# Caurin_CDH_v_1_0.net
KiCad netlist of a schematic drawn in EAGLE
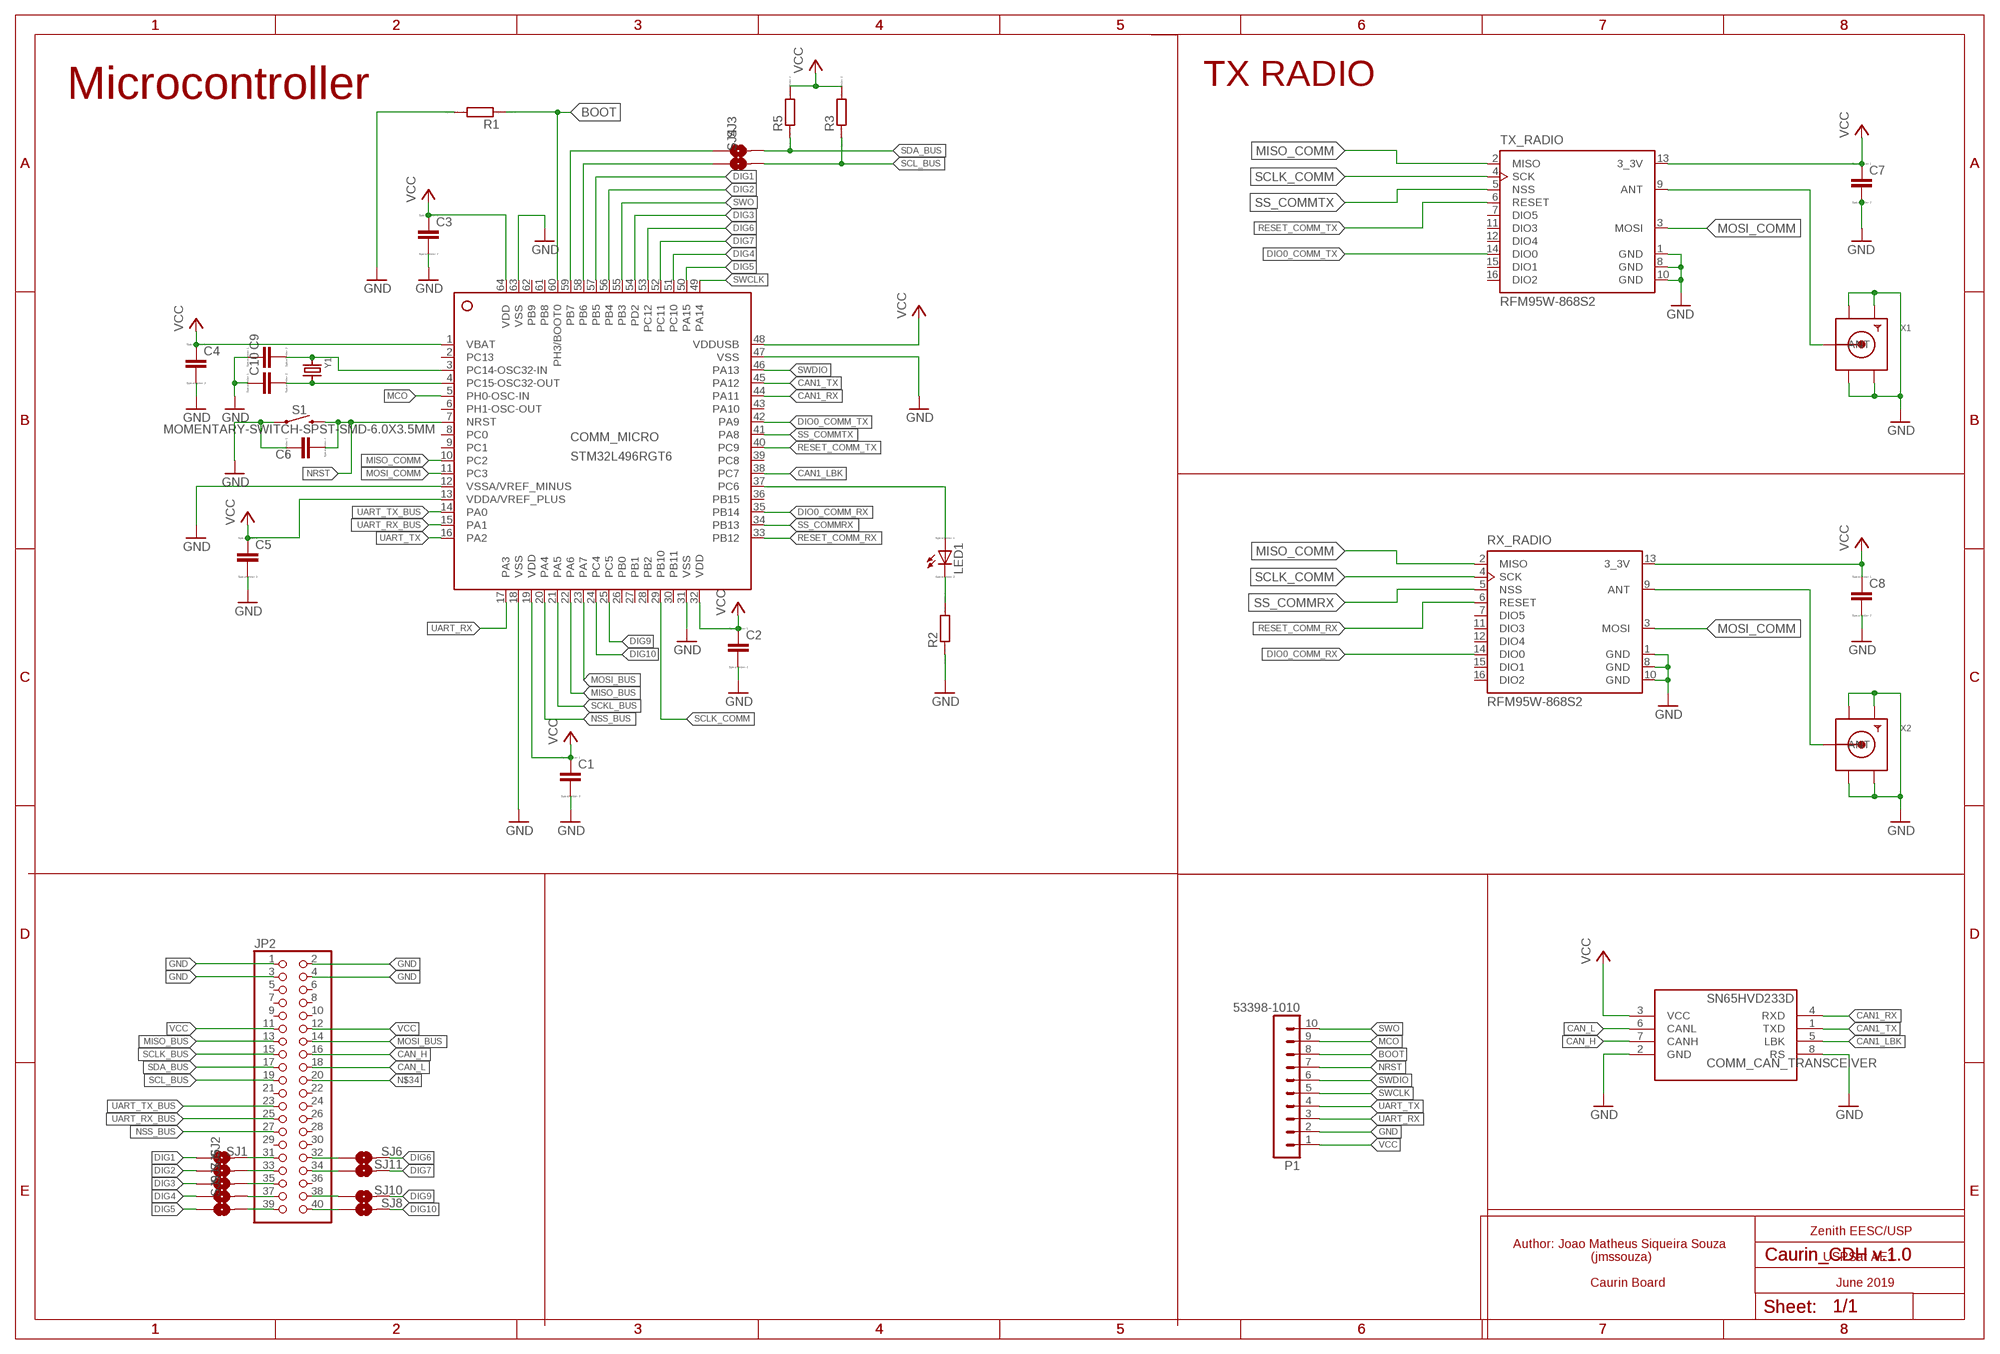
[diagram p0: schematic, sheet 1]

(export (version "E")
  (design (tool "Eeschema 10.0.6"))
  (components
    (comp (ref "C1")
      (value "CC1206")
      (footprint "eagle-import:C1206")
      (libsource (lib "eagle-import") (part "eagle-ltspice_217_CC1206"))
    )
    (comp (ref "C2")
      (value "CC1206")
      (footprint "eagle-import:C1206")
      (libsource (lib "eagle-import") (part "eagle-ltspice_217_CC1206"))
    )
    (comp (ref "C3")
      (value "CC1206")
      (footprint "eagle-import:C1206")
      (libsource (lib "eagle-import") (part "eagle-ltspice_217_CC1206"))
    )
    (comp (ref "C4")
      (value "CC1206")
      (footprint "eagle-import:C1206")
      (libsource (lib "eagle-import") (part "eagle-ltspice_217_CC1206"))
    )
    (comp (ref "C5")
      (value "CC1206")
      (footprint "eagle-import:C1206")
      (libsource (lib "eagle-import") (part "eagle-ltspice_217_CC1206"))
    )
    (comp (ref "C6")
      (value "CC1206")
      (footprint "eagle-import:C1206")
      (libsource (lib "eagle-import") (part "eagle-ltspice_217_CC1206"))
    )
    (comp (ref "C7")
      (value "CC1206")
      (footprint "eagle-import:C1206")
      (libsource (lib "eagle-import") (part "eagle-ltspice_217_CC1206"))
    )
    (comp (ref "C8")
      (value "CC1206")
      (footprint "eagle-import:C1206")
      (libsource (lib "eagle-import") (part "CC1206"))
    )
    (comp (ref "C9")
      (value "CC1206")
      (footprint "eagle-import:C1206")
      (libsource (lib "eagle-import") (part "eagle-ltspice_217_CC1206"))
    )
    (comp (ref "C10")
      (value "CC1206")
      (footprint "eagle-import:C1206")
      (libsource (lib "eagle-import") (part "eagle-ltspice_217_CC1206"))
    )
    (comp (ref "COMM_CAN_TRANSCEIVER")
      (value "SN65HVD233D")
      (footprint "eagle-import:SOIC8")
      (fields (field (name "MF") "Texas Instruments"))
      (libsource (lib "eagle-import") (part "SN65HVD233D"))
    )
    (comp (ref "COMM_MICRO")
      (value "STM32L496RGT6")
      (footprint "eagle-import:LQFP64_10X10")
      (libsource (lib "eagle-import") (part "STM32L496RGT6"))
    )
    (comp (ref "JP2")
      (value "PINHD-2X20")
      (footprint "eagle-import:2X20")
      (libsource (lib "eagle-import") (part "PINHD-2X20"))
    )
    (comp (ref "LED1")
      (value "LED_E")
      (footprint "eagle-import:LED_1206")
      (libsource (lib "eagle-import") (part "LED_E"))
    )
    (comp (ref "P1")
      (value "53398-1010")
      (footprint "eagle-import:53398-1010")
      (libsource (lib "eagle-import") (part "53398-1010"))
    )
    (comp (ref "R1")
      (value "RR1206")
      (footprint "eagle-import:R1206")
      (libsource (lib "eagle-import") (part "RR1206"))
    )
    (comp (ref "R2")
      (value "RR1206")
      (footprint "eagle-import:R1206")
      (libsource (lib "eagle-import") (part "RR1206"))
    )
    (comp (ref "R3")
      (value "RR1206")
      (footprint "eagle-import:R1206")
      (libsource (lib "eagle-import") (part "RR1206"))
    )
    (comp (ref "R5")
      (value "RR1206")
      (footprint "eagle-import:R1206")
      (libsource (lib "eagle-import") (part "RR1206"))
    )
    (comp (ref "RX_RADIO")
      (value "RFM95W-868S2")
      (footprint "eagle-import:XCVR_RFM95W-868S2")
      (fields (field (name "MF") "RF"))
      (libsource (lib "eagle-import") (part "RFM95W-868S2"))
    )
    (comp (ref "S1")
      (value "MOMENTARY-SWITCH-SPST-SMD-6.0X3.5MM")
      (footprint "eagle-import:TACTILE_SWITCH_SMD_6.0X3.5MM")
      (libsource (lib "eagle-import") (part "MOMENTARY-SWITCH-SPST-SMD-6.0X3.5MM"))
    )
    (comp (ref "SJ1")
      (value "SMD-JUMPER-2")
      (footprint "eagle-import:SMD-JUMPER-2")
      (libsource (lib "eagle-import") (part "SMD-JUMPER-2"))
    )
    (comp (ref "SJ2")
      (value "SMD-JUMPER-2")
      (footprint "eagle-import:SMD-JUMPER-2")
      (libsource (lib "eagle-import") (part "SMD-JUMPER-2"))
    )
    (comp (ref "SJ3")
      (value "SMD-JUMPER-2")
      (footprint "eagle-import:SMD-JUMPER-2")
      (libsource (lib "eagle-import") (part "SMD-JUMPER-2"))
    )
    (comp (ref "SJ4")
      (value "SMD-JUMPER-2")
      (footprint "eagle-import:SMD-JUMPER-2")
      (libsource (lib "eagle-import") (part "SMD-JUMPER-2"))
    )
    (comp (ref "SJ5")
      (value "SMD-JUMPER-2")
      (footprint "eagle-import:SMD-JUMPER-2")
      (libsource (lib "eagle-import") (part "SMD-JUMPER-2"))
    )
    (comp (ref "SJ6")
      (value "SMD-JUMPER-2")
      (footprint "eagle-import:SMD-JUMPER-2")
      (libsource (lib "eagle-import") (part "SMD-JUMPER-2"))
    )
    (comp (ref "SJ7")
      (value "SMD-JUMPER-2")
      (footprint "eagle-import:SMD-JUMPER-2")
      (libsource (lib "eagle-import") (part "SMD-JUMPER-2"))
    )
    (comp (ref "SJ8")
      (value "SMD-JUMPER-2")
      (footprint "eagle-import:SMD-JUMPER-2")
      (libsource (lib "eagle-import") (part "SMD-JUMPER-2"))
    )
    (comp (ref "SJ9")
      (value "SMD-JUMPER-2")
      (footprint "eagle-import:SMD-JUMPER-2")
      (libsource (lib "eagle-import") (part "SMD-JUMPER-2"))
    )
    (comp (ref "SJ10")
      (value "SMD-JUMPER-2")
      (footprint "eagle-import:SMD-JUMPER-2")
      (libsource (lib "eagle-import") (part "SMD-JUMPER-2"))
    )
    (comp (ref "SJ11")
      (value "SMD-JUMPER-2")
      (footprint "eagle-import:SMD-JUMPER-2")
      (libsource (lib "eagle-import") (part "SMD-JUMPER-2"))
    )
    (comp (ref "TX_RADIO")
      (value "RFM95W-868S2")
      (footprint "eagle-import:XCVR_RFM95W-868S2")
      (fields (field (name "MF") "RF"))
      (libsource (lib "eagle-import") (part "RFM95W-868S2"))
    )
    (comp (ref "X1")
      (value "SMACONNECTOR")
      (footprint "eagle-import:SMA90_DIP")
      (libsource (lib "eagle-import") (part "SMACONNECTOR"))
    )
    (comp (ref "X2")
      (value "SMACONNECTOR")
      (footprint "eagle-import:SMA90_DIP")
      (libsource (lib "eagle-import") (part "SMACONNECTOR"))
    )
    (comp (ref "Y1")
      (value "CRYSTAL8X3.8SMT")
      (footprint "eagle-import:CRYSTAL_8X3.8")
      (libsource (lib "eagle-import") (part "CRYSTAL8X3.8SMT"))
    )
  )
  (nets
    (net (code "1") (name "BOOT") (class "Default")
      (node (ref "COMM_MICRO") (pin "60") (pinfunction "PH3/BOOT0_60") (pintype "input"))
      (node (ref "P1") (pin "8") (pinfunction "8_8") (pintype "passive"))
      (node (ref "R1") (pin "1") (pinfunction "1_1") (pintype "passive"))
    )
    (net (code "2") (name "CAN1_LBK") (class "Default")
      (node (ref "COMM_CAN_TRANSCEIVER") (pin "5") (pinfunction "LBK_5") (pintype "output"))
      (node (ref "COMM_MICRO") (pin "38") (pinfunction "PC7_38") (pintype "bidirectional"))
    )
    (net (code "3") (name "CAN1_RX") (class "Default")
      (node (ref "COMM_CAN_TRANSCEIVER") (pin "4") (pinfunction "RXD_4") (pintype "output"))
      (node (ref "COMM_MICRO") (pin "44") (pinfunction "PA11_44") (pintype "bidirectional"))
    )
    (net (code "4") (name "CAN1_TX") (class "Default")
      (node (ref "COMM_CAN_TRANSCEIVER") (pin "1") (pinfunction "TXD_1") (pintype "bidirectional"))
      (node (ref "COMM_MICRO") (pin "45") (pinfunction "PA12_45") (pintype "bidirectional"))
    )
    (net (code "5") (name "CAN_H") (class "Default")
      (node (ref "COMM_CAN_TRANSCEIVER") (pin "7") (pinfunction "CANH_7") (pintype "bidirectional"))
      (node (ref "JP2") (pin "16") (pinfunction "16_16") (pintype "passive"))
    )
    (net (code "6") (name "CAN_L") (class "Default")
      (node (ref "COMM_CAN_TRANSCEIVER") (pin "6") (pinfunction "CANL_6") (pintype "bidirectional"))
      (node (ref "JP2") (pin "18") (pinfunction "18_18") (pintype "passive"))
    )
    (net (code "7") (name "DIG1") (class "Default")
      (node (ref "COMM_MICRO") (pin "57") (pinfunction "PB5_57") (pintype "bidirectional"))
      (node (ref "SJ1") (pin "1") (pinfunction "1_1") (pintype "passive"))
    )
    (net (code "8") (name "DIG2") (class "Default")
      (node (ref "COMM_MICRO") (pin "56") (pinfunction "PB4_56") (pintype "input"))
      (node (ref "SJ2") (pin "1") (pinfunction "1_1") (pintype "passive"))
    )
    (net (code "9") (name "DIG3") (class "Default")
      (node (ref "COMM_MICRO") (pin "54") (pinfunction "PD2_54") (pintype "bidirectional"))
      (node (ref "SJ5") (pin "1") (pinfunction "1_1") (pintype "passive"))
    )
    (net (code "10") (name "DIG4") (class "Default")
      (node (ref "COMM_MICRO") (pin "51") (pinfunction "PC10_51") (pintype "bidirectional"))
      (node (ref "SJ7") (pin "1") (pinfunction "1_1") (pintype "passive"))
    )
    (net (code "11") (name "DIG5") (class "Default")
      (node (ref "COMM_MICRO") (pin "50") (pinfunction "PA15_50") (pintype "input"))
      (node (ref "SJ9") (pin "1") (pinfunction "1_1") (pintype "passive"))
    )
    (net (code "12") (name "DIG6") (class "Default")
      (node (ref "COMM_MICRO") (pin "53") (pinfunction "PC12_53") (pintype "bidirectional"))
      (node (ref "SJ6") (pin "2") (pinfunction "2_2") (pintype "passive"))
    )
    (net (code "13") (name "DIG7") (class "Default")
      (node (ref "COMM_MICRO") (pin "52") (pinfunction "PC11_52") (pintype "bidirectional"))
      (node (ref "SJ11") (pin "2") (pinfunction "2_2") (pintype "passive"))
    )
    (net (code "14") (name "DIG9") (class "Default")
      (node (ref "COMM_MICRO") (pin "25") (pinfunction "PC5_25") (pintype "bidirectional"))
      (node (ref "SJ10") (pin "2") (pinfunction "2_2") (pintype "passive"))
    )
    (net (code "15") (name "DIG10") (class "Default")
      (node (ref "COMM_MICRO") (pin "24") (pinfunction "PC4_24") (pintype "bidirectional"))
      (node (ref "SJ8") (pin "2") (pinfunction "2_2") (pintype "passive"))
    )
    (net (code "16") (name "DIO0_COMM_RX") (class "Default")
      (node (ref "COMM_MICRO") (pin "35") (pinfunction "PB14_35") (pintype "bidirectional"))
      (node (ref "RX_RADIO") (pin "14") (pinfunction "DIO0_14") (pintype "bidirectional"))
    )
    (net (code "17") (name "DIO0_COMM_TX") (class "Default")
      (node (ref "COMM_MICRO") (pin "42") (pinfunction "PA9_42") (pintype "bidirectional"))
      (node (ref "TX_RADIO") (pin "14") (pinfunction "DIO0_14") (pintype "bidirectional"))
    )
    (net (code "18") (name "GND") (class "Default")
      (node (ref "C1") (pin "2") (pinfunction "2_2") (pintype "passive"))
      (node (ref "C10") (pin "1") (pinfunction "1_1") (pintype "passive"))
      (node (ref "C2") (pin "2") (pinfunction "2_2") (pintype "passive"))
      (node (ref "C3") (pin "2") (pinfunction "2_2") (pintype "passive"))
      (node (ref "C4") (pin "2") (pinfunction "2_2") (pintype "passive"))
      (node (ref "C5") (pin "2") (pinfunction "2_2") (pintype "passive"))
      (node (ref "C6") (pin "1") (pinfunction "1_1") (pintype "passive"))
      (node (ref "C7") (pin "2") (pinfunction "2_2") (pintype "passive"))
      (node (ref "C8") (pin "2") (pinfunction "2_2") (pintype "passive"))
      (node (ref "C9") (pin "1") (pinfunction "1_1") (pintype "passive"))
      (node (ref "COMM_CAN_TRANSCEIVER") (pin "2") (pinfunction "GND_2") (pintype "power_in"))
      (node (ref "COMM_CAN_TRANSCEIVER") (pin "8") (pinfunction "RS_8") (pintype "input"))
      (node (ref "COMM_MICRO") (pin "12") (pinfunction "VSSA/VREF_MINUS_12") (pintype "passive"))
      (node (ref "COMM_MICRO") (pin "18") (pinfunction "VSS_18") (pintype "power_in"))
      (node (ref "COMM_MICRO") (pin "31") (pinfunction "VSS_31") (pintype "power_in"))
      (node (ref "COMM_MICRO") (pin "47") (pinfunction "VSS_47") (pintype "power_in"))
      (node (ref "COMM_MICRO") (pin "63") (pinfunction "VSS_63") (pintype "power_in"))
      (node (ref "JP2") (pin "1") (pinfunction "1_1") (pintype "passive"))
      (node (ref "JP2") (pin "2") (pinfunction "2_2") (pintype "passive"))
      (node (ref "JP2") (pin "3") (pinfunction "3_3") (pintype "passive"))
      (node (ref "JP2") (pin "4") (pinfunction "4_4") (pintype "passive"))
      (node (ref "P1") (pin "2") (pinfunction "2_2") (pintype "passive"))
      (node (ref "R1") (pin "2") (pinfunction "2_2") (pintype "passive"))
      (node (ref "R2") (pin "1") (pinfunction "1_1") (pintype "passive"))
      (node (ref "RX_RADIO") (pin "1") (pinfunction "GND_1") (pintype "power_in"))
      (node (ref "RX_RADIO") (pin "10") (pinfunction "GND_10") (pintype "power_in"))
      (node (ref "RX_RADIO") (pin "8") (pinfunction "GND_8") (pintype "power_in"))
      (node (ref "S1") (pin "1") (pinfunction "1_1") (pintype "passive"))
      (node (ref "TX_RADIO") (pin "1") (pinfunction "GND_1") (pintype "power_in"))
      (node (ref "TX_RADIO") (pin "10") (pinfunction "GND_10") (pintype "power_in"))
      (node (ref "TX_RADIO") (pin "8") (pinfunction "GND_8") (pintype "power_in"))
      (node (ref "X1") (pin "GND1") (pinfunction "GND1_GND1") (pintype "power_in"))
      (node (ref "X1") (pin "GND2") (pinfunction "GND2_GND2") (pintype "power_in"))
      (node (ref "X1") (pin "GND3") (pinfunction "GND3_GND3") (pintype "power_in"))
      (node (ref "X1") (pin "GND4") (pinfunction "GND4_GND4") (pintype "power_in"))
      (node (ref "X2") (pin "GND1") (pinfunction "GND1_GND1") (pintype "power_in"))
      (node (ref "X2") (pin "GND2") (pinfunction "GND2_GND2") (pintype "power_in"))
      (node (ref "X2") (pin "GND3") (pinfunction "GND3_GND3") (pintype "power_in"))
      (node (ref "X2") (pin "GND4") (pinfunction "GND4_GND4") (pintype "power_in"))
    )
    (net (code "19") (name "MCO") (class "Default")
      (node (ref "COMM_MICRO") (pin "5") (pinfunction "PH0-OSC-IN_5") (pintype "bidirectional"))
      (node (ref "P1") (pin "9") (pinfunction "9_9") (pintype "passive"))
    )
    (net (code "20") (name "MISO_BUS") (class "Default")
      (node (ref "COMM_MICRO") (pin "22") (pinfunction "PA6_22") (pintype "bidirectional"))
      (node (ref "JP2") (pin "13") (pinfunction "13_13") (pintype "passive"))
    )
    (net (code "21") (name "MISO_COMM") (class "Default")
      (node (ref "COMM_MICRO") (pin "10") (pinfunction "PC2_10") (pintype "bidirectional"))
      (node (ref "RX_RADIO") (pin "2") (pinfunction "MISO_2") (pintype "input"))
      (node (ref "TX_RADIO") (pin "2") (pinfunction "MISO_2") (pintype "input"))
    )
    (net (code "22") (name "MOSI_BUS") (class "Default")
      (node (ref "COMM_MICRO") (pin "23") (pinfunction "PA7_23") (pintype "bidirectional"))
      (node (ref "JP2") (pin "14") (pinfunction "14_14") (pintype "passive"))
    )
    (net (code "23") (name "MOSI_COMM") (class "Default")
      (node (ref "COMM_MICRO") (pin "11") (pinfunction "PC3_11") (pintype "bidirectional"))
      (node (ref "RX_RADIO") (pin "3") (pinfunction "MOSI_3") (pintype "output"))
      (node (ref "TX_RADIO") (pin "3") (pinfunction "MOSI_3") (pintype "output"))
    )
    (net (code "24") (name "N$34") (class "Default")
      (node (ref "JP2") (pin "20") (pinfunction "20_20") (pintype "passive"))
    )
    (net (code "25") (name "NRST") (class "Default")
      (node (ref "C6") (pin "2") (pinfunction "2_2") (pintype "passive"))
      (node (ref "COMM_MICRO") (pin "7") (pinfunction "NRST_7") (pintype "input"))
      (node (ref "P1") (pin "7") (pinfunction "7_7") (pintype "passive"))
      (node (ref "S1") (pin "2") (pinfunction "2_2") (pintype "passive"))
    )
    (net (code "26") (name "NSS_BUS") (class "Default")
      (node (ref "COMM_MICRO") (pin "20") (pinfunction "PA4_20") (pintype "bidirectional"))
      (node (ref "JP2") (pin "27") (pinfunction "27_27") (pintype "passive"))
    )
    (net (code "27") (name "Net-(COMM_MICRO-PB6)") (class "Default")
      (node (ref "COMM_MICRO") (pin "58") (pinfunction "PB6_58") (pintype "bidirectional"))
      (node (ref "SJ4") (pin "1") (pinfunction "1_1") (pintype "passive"))
    )
    (net (code "28") (name "Net-(COMM_MICRO-PB7)") (class "Default")
      (node (ref "COMM_MICRO") (pin "59") (pinfunction "PB7_59") (pintype "bidirectional"))
      (node (ref "SJ3") (pin "1") (pinfunction "1_1") (pintype "passive"))
    )
    (net (code "29") (name "Net-(COMM_MICRO-PC6)") (class "Default")
      (node (ref "COMM_MICRO") (pin "37") (pinfunction "PC6_37") (pintype "bidirectional"))
      (node (ref "LED1") (pin "A") (pinfunction "A_A") (pintype "passive"))
    )
    (net (code "30") (name "Net-(COMM_MICRO-PC14-OSC32-IN)") (class "Default")
      (node (ref "C9") (pin "2") (pinfunction "2_2") (pintype "passive"))
      (node (ref "COMM_MICRO") (pin "3") (pinfunction "PC14-OSC32-IN_3") (pintype "bidirectional"))
      (node (ref "Y1") (pin "P$1") (pinfunction "1_P$1") (pintype "passive"))
    )
    (net (code "31") (name "Net-(COMM_MICRO-PC15-OSC32-OUT)") (class "Default")
      (node (ref "C10") (pin "2") (pinfunction "2_2") (pintype "passive"))
      (node (ref "COMM_MICRO") (pin "4") (pinfunction "PC15-OSC32-OUT_4") (pintype "bidirectional"))
      (node (ref "Y1") (pin "P$4") (pinfunction "2_P$4") (pintype "passive"))
    )
    (net (code "32") (name "Net-(JP2-Pad31)") (class "Default")
      (node (ref "JP2") (pin "31") (pinfunction "31_31") (pintype "passive"))
      (node (ref "SJ1") (pin "2") (pinfunction "2_2") (pintype "passive"))
    )
    (net (code "33") (name "Net-(JP2-Pad32)") (class "Default")
      (node (ref "JP2") (pin "32") (pinfunction "32_32") (pintype "passive"))
      (node (ref "SJ6") (pin "1") (pinfunction "1_1") (pintype "passive"))
    )
    (net (code "34") (name "Net-(JP2-Pad33)") (class "Default")
      (node (ref "JP2") (pin "33") (pinfunction "33_33") (pintype "passive"))
      (node (ref "SJ2") (pin "2") (pinfunction "2_2") (pintype "passive"))
    )
    (net (code "35") (name "Net-(JP2-Pad34)") (class "Default")
      (node (ref "JP2") (pin "34") (pinfunction "34_34") (pintype "passive"))
      (node (ref "SJ11") (pin "1") (pinfunction "1_1") (pintype "passive"))
    )
    (net (code "36") (name "Net-(JP2-Pad35)") (class "Default")
      (node (ref "JP2") (pin "35") (pinfunction "35_35") (pintype "passive"))
      (node (ref "SJ5") (pin "2") (pinfunction "2_2") (pintype "passive"))
    )
    (net (code "37") (name "Net-(JP2-Pad37)") (class "Default")
      (node (ref "JP2") (pin "37") (pinfunction "37_37") (pintype "passive"))
      (node (ref "SJ7") (pin "2") (pinfunction "2_2") (pintype "passive"))
    )
    (net (code "38") (name "Net-(JP2-Pad38)") (class "Default")
      (node (ref "JP2") (pin "38") (pinfunction "38_38") (pintype "passive"))
      (node (ref "SJ10") (pin "1") (pinfunction "1_1") (pintype "passive"))
    )
    (net (code "39") (name "Net-(JP2-Pad39)") (class "Default")
      (node (ref "JP2") (pin "39") (pinfunction "39_39") (pintype "passive"))
      (node (ref "SJ9") (pin "2") (pinfunction "2_2") (pintype "passive"))
    )
    (net (code "40") (name "Net-(JP2-Pad40)") (class "Default")
      (node (ref "JP2") (pin "40") (pinfunction "40_40") (pintype "passive"))
      (node (ref "SJ8") (pin "1") (pinfunction "1_1") (pintype "passive"))
    )
    (net (code "41") (name "Net-(LED1-PadC)") (class "Default")
      (node (ref "LED1") (pin "C") (pinfunction "C_C") (pintype "passive"))
      (node (ref "R2") (pin "2") (pinfunction "2_2") (pintype "passive"))
    )
    (net (code "42") (name "Net-(RX_RADIO-ANT)") (class "Default")
      (node (ref "RX_RADIO") (pin "9") (pinfunction "ANT_9") (pintype "passive"))
      (node (ref "X2") (pin "ANTENNA") (pinfunction "ANT_ANTENNA") (pintype "bidirectional"))
    )
    (net (code "43") (name "Net-(TX_RADIO-ANT)") (class "Default")
      (node (ref "TX_RADIO") (pin "9") (pinfunction "ANT_9") (pintype "passive"))
      (node (ref "X1") (pin "ANTENNA") (pinfunction "ANT_ANTENNA") (pintype "bidirectional"))
    )
    (net (code "44") (name "RESET_COMM_RX") (class "Default")
      (node (ref "COMM_MICRO") (pin "33") (pinfunction "PB12_33") (pintype "bidirectional"))
      (node (ref "RX_RADIO") (pin "6") (pinfunction "RESET_6") (pintype "bidirectional"))
    )
    (net (code "45") (name "RESET_COMM_TX") (class "Default")
      (node (ref "COMM_MICRO") (pin "40") (pinfunction "PC9_40") (pintype "bidirectional"))
      (node (ref "TX_RADIO") (pin "6") (pinfunction "RESET_6") (pintype "bidirectional"))
    )
    (net (code "46") (name "SCKL_BUS") (class "Default")
      (node (ref "COMM_MICRO") (pin "21") (pinfunction "PA5_21") (pintype "bidirectional"))
    )
    (net (code "47") (name "SCLK_BUS") (class "Default")
      (node (ref "JP2") (pin "15") (pinfunction "15_15") (pintype "passive"))
    )
    (net (code "48") (name "SCLK_COMM") (class "Default")
      (node (ref "COMM_MICRO") (pin "29") (pinfunction "PB10_29") (pintype "bidirectional"))
      (node (ref "RX_RADIO") (pin "4") (pinfunction "SCK_4") (pintype "input"))
      (node (ref "TX_RADIO") (pin "4") (pinfunction "SCK_4") (pintype "input"))
    )
    (net (code "49") (name "SCL_BUS") (class "Default")
      (node (ref "JP2") (pin "19") (pinfunction "19_19") (pintype "passive"))
      (node (ref "R3") (pin "1") (pinfunction "1_1") (pintype "passive"))
      (node (ref "SJ4") (pin "2") (pinfunction "2_2") (pintype "passive"))
    )
    (net (code "50") (name "SDA_BUS") (class "Default")
      (node (ref "JP2") (pin "17") (pinfunction "17_17") (pintype "passive"))
      (node (ref "R5") (pin "1") (pinfunction "1_1") (pintype "passive"))
      (node (ref "SJ3") (pin "2") (pinfunction "2_2") (pintype "passive"))
    )
    (net (code "51") (name "SS_COMMRX") (class "Default")
      (node (ref "COMM_MICRO") (pin "34") (pinfunction "PB13_34") (pintype "bidirectional"))
      (node (ref "RX_RADIO") (pin "5") (pinfunction "NSS_5") (pintype "input"))
    )
    (net (code "52") (name "SS_COMMTX") (class "Default")
      (node (ref "COMM_MICRO") (pin "41") (pinfunction "PA8_41") (pintype "bidirectional"))
      (node (ref "TX_RADIO") (pin "5") (pinfunction "NSS_5") (pintype "input"))
    )
    (net (code "53") (name "SWCLK") (class "Default")
      (node (ref "COMM_MICRO") (pin "49") (pinfunction "PA14_49") (pintype "input"))
      (node (ref "P1") (pin "5") (pinfunction "5_5") (pintype "passive"))
    )
    (net (code "54") (name "SWDIO") (class "Default")
      (node (ref "COMM_MICRO") (pin "46") (pinfunction "PA13_46") (pintype "input"))
      (node (ref "P1") (pin "6") (pinfunction "6_6") (pintype "passive"))
    )
    (net (code "55") (name "SWO") (class "Default")
      (node (ref "COMM_MICRO") (pin "55") (pinfunction "PB3_55") (pintype "output"))
      (node (ref "P1") (pin "10") (pinfunction "10_10") (pintype "passive"))
    )
    (net (code "56") (name "UART_RX") (class "Default")
      (node (ref "COMM_MICRO") (pin "17") (pinfunction "PA3_17") (pintype "bidirectional"))
      (node (ref "P1") (pin "3") (pinfunction "3_3") (pintype "passive"))
    )
    (net (code "57") (name "UART_RX_BUS") (class "Default")
      (node (ref "COMM_MICRO") (pin "15") (pinfunction "PA1_15") (pintype "bidirectional"))
      (node (ref "JP2") (pin "25") (pinfunction "25_25") (pintype "passive"))
    )
    (net (code "58") (name "UART_TX") (class "Default")
      (node (ref "COMM_MICRO") (pin "16") (pinfunction "PA2_16") (pintype "bidirectional"))
      (node (ref "P1") (pin "4") (pinfunction "4_4") (pintype "passive"))
    )
    (net (code "59") (name "UART_TX_BUS") (class "Default")
      (node (ref "COMM_MICRO") (pin "14") (pinfunction "PA0_14") (pintype "bidirectional"))
      (node (ref "JP2") (pin "23") (pinfunction "23_23") (pintype "passive"))
    )
    (net (code "60") (name "VCC") (class "Default")
      (node (ref "C1") (pin "1") (pinfunction "1_1") (pintype "passive"))
      (node (ref "C2") (pin "1") (pinfunction "1_1") (pintype "passive"))
      (node (ref "C3") (pin "1") (pinfunction "1_1") (pintype "passive"))
      (node (ref "C4") (pin "1") (pinfunction "1_1") (pintype "passive"))
      (node (ref "C5") (pin "1") (pinfunction "1_1") (pintype "passive"))
      (node (ref "C7") (pin "1") (pinfunction "1_1") (pintype "passive"))
      (node (ref "C8") (pin "1") (pinfunction "1_1") (pintype "passive"))
      (node (ref "COMM_CAN_TRANSCEIVER") (pin "3") (pinfunction "VCC_3") (pintype "power_in"))
      (node (ref "COMM_MICRO") (pin "1") (pinfunction "VBAT_1") (pintype "passive"))
      (node (ref "COMM_MICRO") (pin "13") (pinfunction "VDDA/VREF_PLUS_13") (pintype "passive"))
      (node (ref "COMM_MICRO") (pin "19") (pinfunction "VDD_19") (pintype "power_in"))
      (node (ref "COMM_MICRO") (pin "32") (pinfunction "VDD_32") (pintype "power_in"))
      (node (ref "COMM_MICRO") (pin "48") (pinfunction "VDDUSB_48") (pintype "bidirectional"))
      (node (ref "COMM_MICRO") (pin "64") (pinfunction "VDD_64") (pintype "power_in"))
      (node (ref "JP2") (pin "11") (pinfunction "11_11") (pintype "passive"))
      (node (ref "JP2") (pin "12") (pinfunction "12_12") (pintype "passive"))
      (node (ref "P1") (pin "1") (pinfunction "1_1") (pintype "passive"))
      (node (ref "R3") (pin "2") (pinfunction "2_2") (pintype "passive"))
      (node (ref "R5") (pin "2") (pinfunction "2_2") (pintype "passive"))
      (node (ref "RX_RADIO") (pin "13") (pinfunction "3_3V_13") (pintype "power_in"))
      (node (ref "TX_RADIO") (pin "13") (pinfunction "3_3V_13") (pintype "power_in"))
    )
    (net (code "61") (name "unconnected-(COMM_MICRO-PA10-Pad43)") (class "Default")
      (node (ref "COMM_MICRO") (pin "43") (pinfunction "PA10_43") (pintype "bidirectional"))
    )
    (net (code "62") (name "unconnected-(COMM_MICRO-PB0-Pad26)") (class "Default")
      (node (ref "COMM_MICRO") (pin "26") (pinfunction "PB0_26") (pintype "bidirectional"))
    )
    (net (code "63") (name "unconnected-(COMM_MICRO-PB1-Pad27)") (class "Default")
      (node (ref "COMM_MICRO") (pin "27") (pinfunction "PB1_27") (pintype "bidirectional"))
    )
    (net (code "64") (name "unconnected-(COMM_MICRO-PB2-Pad28)") (class "Default")
      (node (ref "COMM_MICRO") (pin "28") (pinfunction "PB2_28") (pintype "bidirectional"))
    )
    (net (code "65") (name "unconnected-(COMM_MICRO-PB8-Pad61)") (class "Default")
      (node (ref "COMM_MICRO") (pin "61") (pinfunction "PB8_61") (pintype "bidirectional"))
    )
    (net (code "66") (name "unconnected-(COMM_MICRO-PB9-Pad62)") (class "Default")
      (node (ref "COMM_MICRO") (pin "62") (pinfunction "PB9_62") (pintype "bidirectional"))
    )
    (net (code "67") (name "unconnected-(COMM_MICRO-PB11-Pad30)") (class "Default")
      (node (ref "COMM_MICRO") (pin "30") (pinfunction "PB11_30") (pintype "bidirectional"))
    )
    (net (code "68") (name "unconnected-(COMM_MICRO-PB15-Pad36)") (class "Default")
      (node (ref "COMM_MICRO") (pin "36") (pinfunction "PB15_36") (pintype "bidirectional"))
    )
    (net (code "69") (name "unconnected-(COMM_MICRO-PC0-Pad8)") (class "Default")
      (node (ref "COMM_MICRO") (pin "8") (pinfunction "PC0_8") (pintype "bidirectional"))
    )
    (net (code "70") (name "unconnected-(COMM_MICRO-PC1-Pad9)") (class "Default")
      (node (ref "COMM_MICRO") (pin "9") (pinfunction "PC1_9") (pintype "bidirectional"))
    )
    (net (code "71") (name "unconnected-(COMM_MICRO-PC8-Pad39)") (class "Default")
      (node (ref "COMM_MICRO") (pin "39") (pinfunction "PC8_39") (pintype "bidirectional"))
    )
    (net (code "72") (name "unconnected-(COMM_MICRO-PC13-Pad2)") (class "Default")
      (node (ref "COMM_MICRO") (pin "2") (pinfunction "PC13_2") (pintype "bidirectional"))
    )
    (net (code "73") (name "unconnected-(COMM_MICRO-PH1-OSC-OUT-Pad6)") (class "Default")
      (node (ref "COMM_MICRO") (pin "6") (pinfunction "PH1-OSC-OUT_6") (pintype "bidirectional"))
    )
    (net (code "74") (name "unconnected-(JP2-Pad5)") (class "Default")
      (node (ref "JP2") (pin "5") (pinfunction "5_5") (pintype "passive"))
    )
    (net (code "75") (name "unconnected-(JP2-Pad6)") (class "Default")
      (node (ref "JP2") (pin "6") (pinfunction "6_6") (pintype "passive"))
    )
    (net (code "76") (name "unconnected-(JP2-Pad7)") (class "Default")
      (node (ref "JP2") (pin "7") (pinfunction "7_7") (pintype "passive"))
    )
    (net (code "77") (name "unconnected-(JP2-Pad8)") (class "Default")
      (node (ref "JP2") (pin "8") (pinfunction "8_8") (pintype "passive"))
    )
    (net (code "78") (name "unconnected-(JP2-Pad9)") (class "Default")
      (node (ref "JP2") (pin "9") (pinfunction "9_9") (pintype "passive"))
    )
    (net (code "79") (name "unconnected-(JP2-Pad10)") (class "Default")
      (node (ref "JP2") (pin "10") (pinfunction "10_10") (pintype "passive"))
    )
    (net (code "80") (name "unconnected-(JP2-Pad21)") (class "Default")
      (node (ref "JP2") (pin "21") (pinfunction "21_21") (pintype "passive"))
    )
    (net (code "81") (name "unconnected-(JP2-Pad22)") (class "Default")
      (node (ref "JP2") (pin "22") (pinfunction "22_22") (pintype "passive"))
    )
    (net (code "82") (name "unconnected-(JP2-Pad24)") (class "Default")
      (node (ref "JP2") (pin "24") (pinfunction "24_24") (pintype "passive"))
    )
    (net (code "83") (name "unconnected-(JP2-Pad26)") (class "Default")
      (node (ref "JP2") (pin "26") (pinfunction "26_26") (pintype "passive"))
    )
    (net (code "84") (name "unconnected-(JP2-Pad28)") (class "Default")
      (node (ref "JP2") (pin "28") (pinfunction "28_28") (pintype "passive"))
    )
    (net (code "85") (name "unconnected-(JP2-Pad29)") (class "Default")
      (node (ref "JP2") (pin "29") (pinfunction "29_29") (pintype "passive"))
    )
    (net (code "86") (name "unconnected-(JP2-Pad30)") (class "Default")
      (node (ref "JP2") (pin "30") (pinfunction "30_30") (pintype "passive"))
    )
    (net (code "87") (name "unconnected-(JP2-Pad36)") (class "Default")
      (node (ref "JP2") (pin "36") (pinfunction "36_36") (pintype "passive"))
    )
    (net (code "88") (name "unconnected-(RX_RADIO-DIO1-Pad15)") (class "Default")
      (node (ref "RX_RADIO") (pin "15") (pinfunction "DIO1_15") (pintype "bidirectional"))
    )
    (net (code "89") (name "unconnected-(RX_RADIO-DIO2-Pad16)") (class "Default")
      (node (ref "RX_RADIO") (pin "16") (pinfunction "DIO2_16") (pintype "bidirectional"))
    )
    (net (code "90") (name "unconnected-(RX_RADIO-DIO3-Pad11)") (class "Default")
      (node (ref "RX_RADIO") (pin "11") (pinfunction "DIO3_11") (pintype "bidirectional"))
    )
    (net (code "91") (name "unconnected-(RX_RADIO-DIO4-Pad12)") (class "Default")
      (node (ref "RX_RADIO") (pin "12") (pinfunction "DIO4_12") (pintype "bidirectional"))
    )
    (net (code "92") (name "unconnected-(RX_RADIO-DIO5-Pad7)") (class "Default")
      (node (ref "RX_RADIO") (pin "7") (pinfunction "DIO5_7") (pintype "bidirectional"))
    )
    (net (code "93") (name "unconnected-(TX_RADIO-DIO1-Pad15)") (class "Default")
      (node (ref "TX_RADIO") (pin "15") (pinfunction "DIO1_15") (pintype "bidirectional"))
    )
    (net (code "94") (name "unconnected-(TX_RADIO-DIO2-Pad16)") (class "Default")
      (node (ref "TX_RADIO") (pin "16") (pinfunction "DIO2_16") (pintype "bidirectional"))
    )
    (net (code "95") (name "unconnected-(TX_RADIO-DIO3-Pad11)") (class "Default")
      (node (ref "TX_RADIO") (pin "11") (pinfunction "DIO3_11") (pintype "bidirectional"))
    )
    (net (code "96") (name "unconnected-(TX_RADIO-DIO4-Pad12)") (class "Default")
      (node (ref "TX_RADIO") (pin "12") (pinfunction "DIO4_12") (pintype "bidirectional"))
    )
    (net (code "97") (name "unconnected-(TX_RADIO-DIO5-Pad7)") (class "Default")
      (node (ref "TX_RADIO") (pin "7") (pinfunction "DIO5_7") (pintype "bidirectional"))
    )
  )
)
